# Electron.net
KiCad netlist of a schematic drawn in Altium Designer
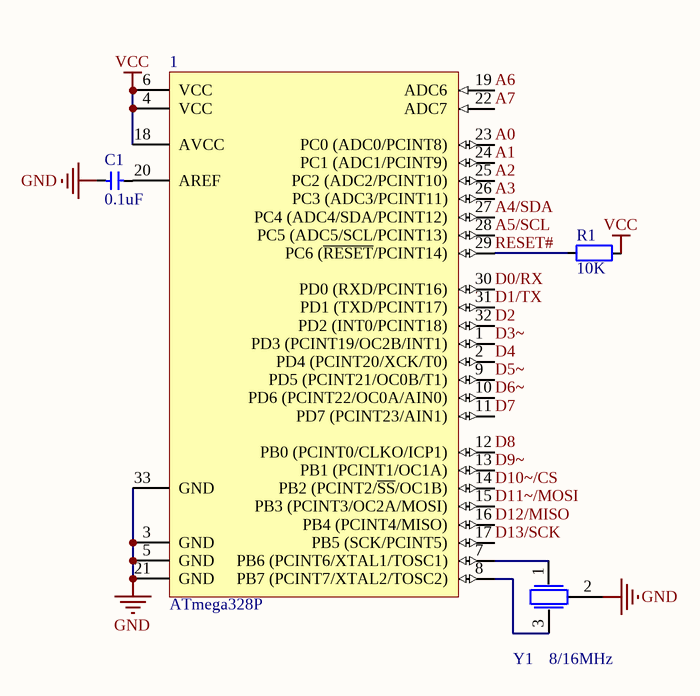
[diagram p0: Electron.SchDoc]

(export (version "E")
  (design (tool "Eeschema 10.0.6"))
  (components
    (comp (ref "1")
      (value "ATmega328P")
      (footprint "QFN-32")
      (description "MCU")
      (libsource (lib "MyPcbLib") (part "ATmega328P"))
    )
    (comp (ref "C1")
      (value "0.1uF")
      (footprint "CAP_0402")
      (description "Capacitor")
      (libsource (lib "MyPcbLib") (part "电容-0402"))
    )
    (comp (ref "R1")
      (value "10K")
      (footprint "RES_0402")
      (description "Resistor")
      (libsource (lib "MyPcbLib") (part "电阻-0402"))
    )
    (comp (ref "Y1")
      (value "8/16MHz")
      (footprint "晶振-3P")
      (description "村田贴片")
      (libsource (lib "MyPcbLib") (part "晶振-3Pin"))
    )
  )
  (nets
    (net (code "1") (name "/A0") (class "Default")
      (node (ref "1") (pin "23") (pinfunction "PC0_(ADC0/PCINT8)_23") (pintype "bidirectional"))
    )
    (net (code "2") (name "/A1") (class "Default")
      (node (ref "1") (pin "24") (pinfunction "PC1_(ADC1/PCINT9)_24") (pintype "bidirectional"))
    )
    (net (code "3") (name "/A2") (class "Default")
      (node (ref "1") (pin "25") (pinfunction "PC2_(ADC2/PCINT10)_25") (pintype "bidirectional"))
    )
    (net (code "4") (name "/A3") (class "Default")
      (node (ref "1") (pin "26") (pinfunction "PC3_(ADC3/PCINT11)_26") (pintype "bidirectional"))
    )
    (net (code "5") (name "/A4{slash}SDA") (class "Default")
      (node (ref "1") (pin "27") (pinfunction "PC4_(ADC4/SDA/PCINT12)_27") (pintype "bidirectional"))
    )
    (net (code "6") (name "/A5{slash}SCL") (class "Default")
      (node (ref "1") (pin "28") (pinfunction "PC5_(ADC5/SCL/PCINT13)_28") (pintype "bidirectional"))
    )
    (net (code "7") (name "/A6") (class "Default")
      (node (ref "1") (pin "19") (pinfunction "ADC6_19") (pintype "input"))
    )
    (net (code "8") (name "/A7") (class "Default")
      (node (ref "1") (pin "22") (pinfunction "ADC7_22") (pintype "input"))
    )
    (net (code "9") (name "/D0{slash}RX") (class "Default")
      (node (ref "1") (pin "30") (pinfunction "PD0_(RXD/PCINT16)_30") (pintype "bidirectional"))
    )
    (net (code "10") (name "/D1{slash}TX") (class "Default")
      (node (ref "1") (pin "31") (pinfunction "PD1_(TXD/PCINT17)_31") (pintype "bidirectional"))
    )
    (net (code "11") (name "/D2") (class "Default")
      (node (ref "1") (pin "32") (pinfunction "PD2_(INT0/PCINT18)_32") (pintype "bidirectional"))
    )
    (net (code "12") (name "/D3~") (class "Default")
      (node (ref "1") (pin "1") (pinfunction "PD3_(PCINT19/OC2B/INT1)_1") (pintype "bidirectional"))
    )
    (net (code "13") (name "/D4") (class "Default")
      (node (ref "1") (pin "2") (pinfunction "PD4_(PCINT20/XCK/T0)_2") (pintype "bidirectional"))
    )
    (net (code "14") (name "/D5~") (class "Default")
      (node (ref "1") (pin "9") (pinfunction "PD5_(PCINT21/OC0B/T1)_9") (pintype "bidirectional"))
    )
    (net (code "15") (name "/D6~") (class "Default")
      (node (ref "1") (pin "10") (pinfunction "PD6_(PCINT22/OC0A/AIN0)_10") (pintype "bidirectional"))
    )
    (net (code "16") (name "/D7") (class "Default")
      (node (ref "1") (pin "11") (pinfunction "PD7_(PCINT23/AIN1)_11") (pintype "bidirectional"))
    )
    (net (code "17") (name "/D8") (class "Default")
      (node (ref "1") (pin "12") (pinfunction "PB0_(PCINT0/CLKO/ICP1)_12") (pintype "bidirectional"))
    )
    (net (code "18") (name "/D9~") (class "Default")
      (node (ref "1") (pin "13") (pinfunction "PB1_(PCINT1/OC1A)_13") (pintype "bidirectional"))
    )
    (net (code "19") (name "/D10~{slash}CS") (class "Default")
      (node (ref "1") (pin "14") (pinfunction "PB2_(PCINT2/~{SS}/OC1B)_14") (pintype "bidirectional"))
    )
    (net (code "20") (name "/D11~{slash}MOSI") (class "Default")
      (node (ref "1") (pin "15") (pinfunction "PB3_(PCINT3/OC2A/MOSI)_15") (pintype "bidirectional"))
    )
    (net (code "21") (name "/D12{slash}MISO") (class "Default")
      (node (ref "1") (pin "16") (pinfunction "PB4_(PCINT4/MISO)_16") (pintype "bidirectional"))
    )
    (net (code "22") (name "/D13{slash}SCK") (class "Default")
      (node (ref "1") (pin "17") (pinfunction "PB5_(SCK/PCINT5)_17") (pintype "bidirectional"))
    )
    (net (code "23") (name "/RESET#") (class "Default")
      (node (ref "1") (pin "29") (pinfunction "PC6_(~{RESET}/PCINT14)_29") (pintype "bidirectional"))
      (node (ref "R1") (pin "1") (pinfunction "1_1") (pintype "passive"))
    )
    (net (code "24") (name "GND") (class "Default")
      (node (ref "1") (pin "21") (pinfunction "GND_21") (pintype "power_in"))
      (node (ref "1") (pin "3") (pinfunction "GND_3") (pintype "power_in"))
      (node (ref "1") (pin "33") (pinfunction "GND_33") (pintype "passive"))
      (node (ref "1") (pin "5") (pinfunction "GND_5") (pintype "power_in"))
      (node (ref "C1") (pin "2") (pinfunction "2_2") (pintype "passive"))
      (node (ref "Y1") (pin "2") (pinfunction "2_2") (pintype "passive"))
    )
    (net (code "25") (name "Net-(1-AREF)") (class "Default")
      (node (ref "1") (pin "20") (pinfunction "AREF_20") (pintype "passive"))
      (node (ref "C1") (pin "1") (pinfunction "1_1") (pintype "passive"))
    )
    (net (code "26") (name "Net-(1-PB6_(PCINT6{slash}XTAL1{slash}TOSC1))") (class "Default")
      (node (ref "1") (pin "7") (pinfunction "PB6_(PCINT6/XTAL1/TOSC1)_7") (pintype "bidirectional"))
      (node (ref "Y1") (pin "1") (pinfunction "1_1") (pintype "passive"))
    )
    (net (code "27") (name "Net-(1-PB7_(PCINT7{slash}XTAL2{slash}TOSC2))") (class "Default")
      (node (ref "1") (pin "8") (pinfunction "PB7_(PCINT7/XTAL2/TOSC2)_8") (pintype "bidirectional"))
      (node (ref "Y1") (pin "3") (pinfunction "3_3") (pintype "passive"))
    )
    (net (code "28") (name "VCC") (class "Default")
      (node (ref "1") (pin "18") (pinfunction "AVCC_18") (pintype "power_in"))
      (node (ref "1") (pin "4") (pinfunction "VCC_4") (pintype "power_in"))
      (node (ref "1") (pin "6") (pinfunction "VCC_6") (pintype "power_in"))
      (node (ref "R1") (pin "2") (pinfunction "2_2") (pintype "passive"))
    )
  )
)
